# PWR.net
KiCad netlist of a schematic drawn in Altium Designer
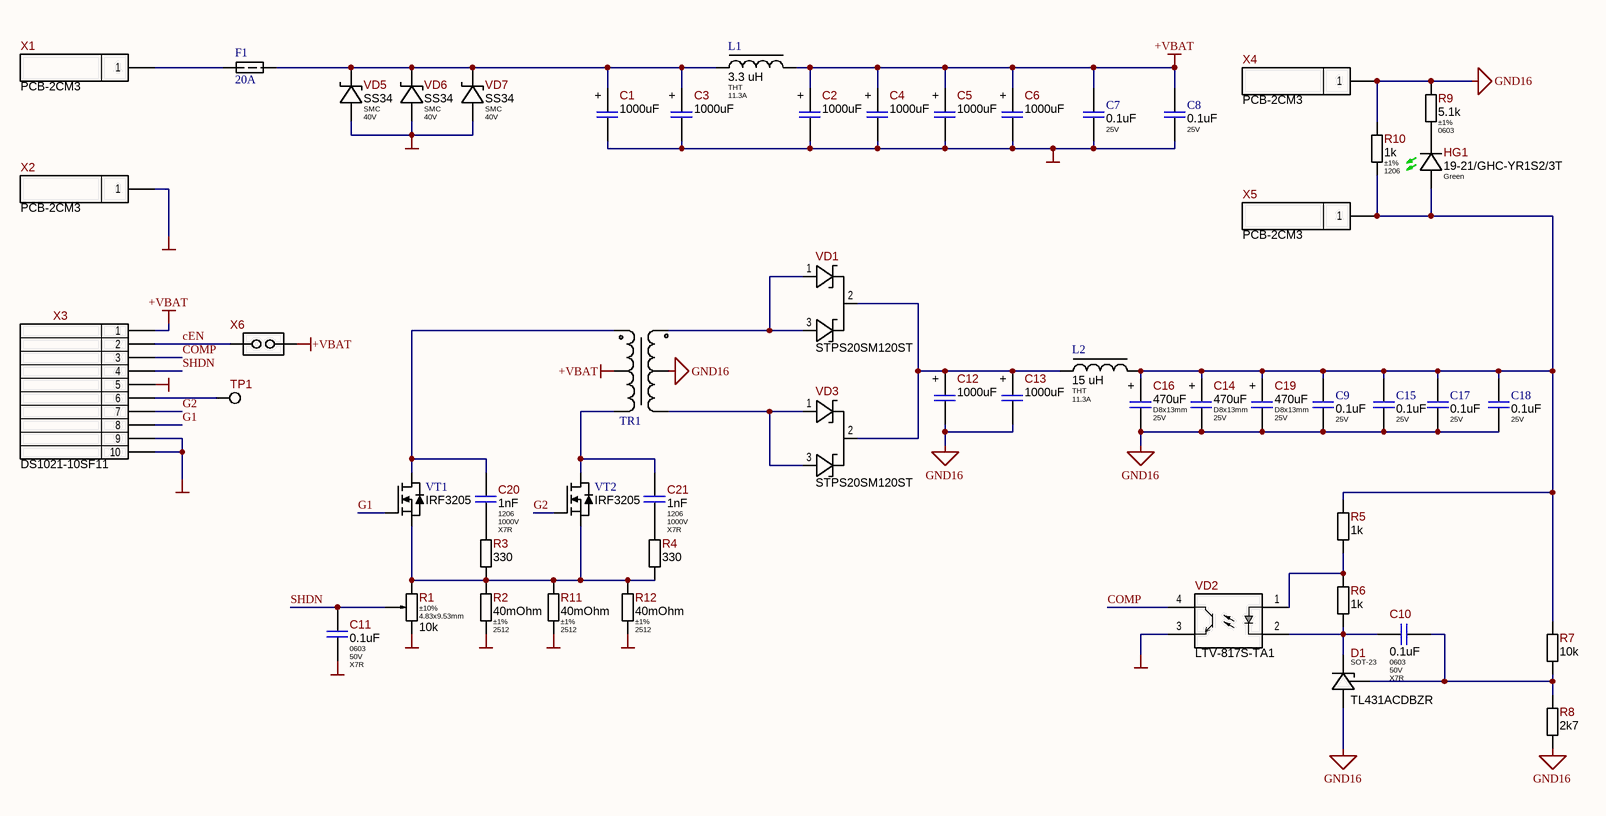
[diagram p0: PWR.SchDoc]

(export (version "E")
  (design (tool "Eeschema 10.0.6"))
  (components
    (comp (ref "C1")
      (value "1000uF")
      (footprint "CAP-AE-PTH-100D05x200H20")
      (description "1000uF 25V ±20% Aluminum Electrolytic Capacitors Radial, 2000 Hrs @ 105°C, 740mA Ripple Current")
      (fields (field (name "VOLTAGE") "25V") (field (name "PART NUMBER") "ESH108M025AH4AA"))
      (libsource (lib "capacitors") (part "ESH108M025AH4AA"))
    )
    (comp (ref "C2")
      (value "1000uF")
      (footprint "CAP-AE-PTH-100D05x200H20")
      (description "1000uF 25V ±20% Aluminum Electrolytic Capacitors Radial, 2000 Hrs @ 105°C, 740mA Ripple Current")
      (fields (field (name "VOLTAGE") "25V") (field (name "PART NUMBER") "ESH108M025AH4AA"))
      (libsource (lib "capacitors") (part "ESH108M025AH4AA"))
    )
    (comp (ref "C3")
      (value "1000uF")
      (footprint "CAP-AE-PTH-100D05x200H20")
      (description "1000uF 25V ±20% Aluminum Electrolytic Capacitors Radial, 2000 Hrs @ 105°C, 740mA Ripple Current")
      (fields (field (name "VOLTAGE") "25V") (field (name "PART NUMBER") "ESH108M025AH4AA"))
      (libsource (lib "capacitors") (part "ESH108M025AH4AA"))
    )
    (comp (ref "C4")
      (value "1000uF")
      (footprint "CAP-AE-PTH-100D05x200H20")
      (description "1000uF 25V ±20% Aluminum Electrolytic Capacitors Radial, 2000 Hrs @ 105°C, 740mA Ripple Current")
      (fields (field (name "VOLTAGE") "25V") (field (name "PART NUMBER") "ESH108M025AH4AA"))
      (libsource (lib "capacitors") (part "ESH108M025AH4AA"))
    )
    (comp (ref "C5")
      (value "1000uF")
      (footprint "CAP-AE-PTH-100D05x200H20")
      (description "1000uF 25V ±20% Aluminum Electrolytic Capacitors Radial, 2000 Hrs @ 105°C, 740mA Ripple Current")
      (fields (field (name "VOLTAGE") "25V") (field (name "PART NUMBER") "ESH108M025AH4AA"))
      (libsource (lib "capacitors") (part "ESH108M025AH4AA"))
    )
    (comp (ref "C6")
      (value "1000uF")
      (footprint "CAP-AE-PTH-100D05x200H20")
      (description "1000uF 25V ±20% Aluminum Electrolytic Capacitors Radial, 2000 Hrs @ 105°C, 740mA Ripple Current")
      (fields (field (name "VOLTAGE") "25V") (field (name "PART NUMBER") "ESH108M025AH4AA"))
      (libsource (lib "capacitors") (part "ESH108M025AH4AA"))
    )
    (comp (ref "C7")
      (value "0.1uF")
      (footprint "CAP: MKS2 (W=2.50MM)")
      (description "Multilayer Ceramic Capacitors MLCC - SMD/SMT 10 uF 25 VDC 10% 1206 X7R")
      (fields
        (field (name "MANUFACTURER") "Murata")
        (field (name "PART NUMBER") "GRM31CR71E106KA12L")
        (field (name "VOLTAGE") "25V")
      )
      (libsource (lib "vitech_capacitors") (part "CAP_NON_POLAR_THT"))
    )
    (comp (ref "C8")
      (value "0.1uF")
      (footprint "CAP: MKS2 (W=2.50MM)")
      (description "Multilayer Ceramic Capacitors MLCC - SMD/SMT 10 uF 25 VDC 10% 1206 X7R")
      (fields
        (field (name "MANUFACTURER") "Murata")
        (field (name "PART NUMBER") "GRM31CR71E106KA12L")
        (field (name "VOLTAGE") "25V")
      )
      (libsource (lib "vitech_capacitors") (part "CAP_NON_POLAR_THT"))
    )
    (comp (ref "C9")
      (value "0.1uF")
      (footprint "CAP: MKS2 (W=2.50MM)")
      (description "Multilayer Ceramic Capacitors MLCC - SMD/SMT 10 uF 25 VDC 10% 1206 X7R")
      (fields
        (field (name "MANUFACTURER") "Murata")
        (field (name "PART NUMBER") "GRM31CR71E106KA12L")
        (field (name "VOLTAGE") "25V")
      )
      (libsource (lib "vitech_capacitors") (part "CAP_NON_POLAR_THT"))
    )
    (comp (ref "C10")
      (value "0.1uF")
      (footprint "C_CERAMIC_0603_MED")
      (description "100nF 50V X7R ±10% 0603 Ceramic Capacitor RoHS")
      (fields
        (field (name "PACKAGE") "0603")
        (field (name "VOLTAGE") "50V")
        (field (name "DIELECTRIC TYPE") "X7R")
        (field (name "PART NUMBER") "CL10B104KB8NNNC")
        (field (name "MANUFACTURER") "Samsung Electro-Mechanics")
      )
      (libsource (lib "capacitors") (part "CL10B104KB8NNNC"))
    )
    (comp (ref "C11")
      (value "0.1uF")
      (footprint "C_CERAMIC_0603_MED")
      (description "100nF 50V X7R ±10% 0603 Ceramic Capacitor RoHS")
      (fields
        (field (name "PACKAGE") "0603")
        (field (name "VOLTAGE") "50V")
        (field (name "DIELECTRIC TYPE") "X7R")
        (field (name "PART NUMBER") "CL10B104KB8NNNC")
        (field (name "MANUFACTURER") "Samsung Electro-Mechanics")
      )
      (libsource (lib "capacitors") (part "CL10B104KB8NNNC"))
    )
    (comp (ref "C12")
      (value "1000uF")
      (footprint "CAP-AE-PTH-100D05x200H20")
      (description "1000uF 25V ±20% Aluminum Electrolytic Capacitors Radial, 2000 Hrs @ 105°C, 740mA Ripple Current")
      (fields (field (name "VOLTAGE") "25V") (field (name "PART NUMBER") "ESH108M025AH4AA"))
      (libsource (lib "capacitors") (part "ESH108M025AH4AA"))
    )
    (comp (ref "C13")
      (value "1000uF")
      (footprint "CAP-AE-PTH-100D05x200H20")
      (description "1000uF 25V ±20% Aluminum Electrolytic Capacitors Radial, 2000 Hrs @ 105°C, 740mA Ripple Current")
      (fields (field (name "VOLTAGE") "25V") (field (name "PART NUMBER") "ESH108M025AH4AA"))
      (libsource (lib "capacitors") (part "ESH108M025AH4AA"))
    )
    (comp (ref "C14")
      (value "470uF")
      (footprint "CAP-AE-PTH-80D05x130H15")
      (fields
        (field (name "PACKAGE") "D8x13mm")
        (field (name "VOLTAGE") "25V")
        (field (name "PART NUMBER") "KS-025V471MF130")
        (field (name "MANUFACTURER") "Koshin")
        (field (name "TOLERANCE") "±20%")
      )
      (libsource (lib "capacitors") (part "KS-025V471MF130"))
    )
    (comp (ref "C15")
      (value "0.1uF")
      (footprint "CAP: MKS2 (W=2.50MM)")
      (description "Multilayer Ceramic Capacitors MLCC - SMD/SMT 10 uF 25 VDC 10% 1206 X7R")
      (fields
        (field (name "MANUFACTURER") "Murata")
        (field (name "PART NUMBER") "GRM31CR71E106KA12L")
        (field (name "VOLTAGE") "25V")
      )
      (libsource (lib "vitech_capacitors") (part "CAP_NON_POLAR_THT"))
    )
    (comp (ref "C16")
      (value "470uF")
      (footprint "CAP-AE-PTH-80D05x130H15")
      (fields
        (field (name "PACKAGE") "D8x13mm")
        (field (name "VOLTAGE") "25V")
        (field (name "PART NUMBER") "KS-025V471MF130")
        (field (name "MANUFACTURER") "Koshin")
        (field (name "TOLERANCE") "±20%")
      )
      (libsource (lib "capacitors") (part "KS-025V471MF130"))
    )
    (comp (ref "C17")
      (value "0.1uF")
      (footprint "CAP: MKS2 (W=2.50MM)")
      (description "Multilayer Ceramic Capacitors MLCC - SMD/SMT 10 uF 25 VDC 10% 1206 X7R")
      (fields
        (field (name "MANUFACTURER") "Murata")
        (field (name "PART NUMBER") "GRM31CR71E106KA12L")
        (field (name "VOLTAGE") "25V")
      )
      (libsource (lib "vitech_capacitors") (part "CAP_NON_POLAR_THT"))
    )
    (comp (ref "C18")
      (value "0.1uF")
      (footprint "CAP: MKS2 (W=2.50MM)")
      (description "Multilayer Ceramic Capacitors MLCC - SMD/SMT 10 uF 25 VDC 10% 1206 X7R")
      (fields
        (field (name "MANUFACTURER") "Murata")
        (field (name "PART NUMBER") "GRM31CR71E106KA12L")
        (field (name "VOLTAGE") "25V")
      )
      (libsource (lib "vitech_capacitors") (part "CAP_NON_POLAR_THT"))
    )
    (comp (ref "C19")
      (value "470uF")
      (footprint "CAP-AE-PTH-80D05x130H15")
      (fields
        (field (name "PACKAGE") "D8x13mm")
        (field (name "VOLTAGE") "25V")
        (field (name "PART NUMBER") "KS-025V471MF130")
        (field (name "MANUFACTURER") "Koshin")
        (field (name "TOLERANCE") "±20%")
      )
      (libsource (lib "capacitors") (part "KS-025V471MF130"))
    )
    (comp (ref "C20")
      (value "1nF")
      (footprint "C_CERAMIC_1206_MED")
      (description "1nF 1000V X7R ±10% 1206 Ceramic Capacitor RoHS")
      (fields
        (field (name "PACKAGE") "1206")
        (field (name "VOLTAGE") "1000V")
        (field (name "DIELECTRIC TYPE") "X7R")
        (field (name "PART NUMBER") "1206B102K102CG")
        (field (name "MANUFACTURER") "Walsin")
      )
      (libsource (lib "capacitors") (part "1206B102K102CG"))
    )
    (comp (ref "C21")
      (value "1nF")
      (footprint "C_CERAMIC_1206_MED")
      (description "1nF 1000V X7R ±10% 1206 Ceramic Capacitor RoHS")
      (fields
        (field (name "PACKAGE") "1206")
        (field (name "VOLTAGE") "1000V")
        (field (name "DIELECTRIC TYPE") "X7R")
        (field (name "PART NUMBER") "1206B102K102CG")
        (field (name "MANUFACTURER") "Walsin")
      )
      (libsource (lib "capacitors") (part "1206B102K102CG"))
    )
    (comp (ref "D1")
      (value "TL431ACDBZR")
      (footprint "SOT-23_MED")
      (description "Adjustable Precision Shunt Regulator, Accuracy 1%,  SOT-23-3")
      (fields
        (field (name "PACKAGE") "SOT-23")
        (field (name "PART NUMBER") "TL431ACDBZR")
        (field (name "MANUFACTURER") "Texas Instruments")
      )
      (libsource (lib "ic") (part "TL431ACDBZR"))
    )
    (comp (ref "F1")
      (value "20A")
      (footprint "MINI_FUSE")
      (description "Fuse MAXI Size")
      (fields (field (name "MANUFACTURER_PART_NUMBER") "17861640001"))
      (libsource (lib "vitech_fuses") (part "MINI_FUSE"))
    )
    (comp (ref "HG1")
      (value "19-21/GHC-YR1S2/3T")
      (footprint "LED-0603G-0.8mm")
      (description "Indication LED, Green 528nm, Clear, SMD 0603, Vf 2.7-3.7V, 112 - 285mcd @ 20mA, 110°")
      (fields
        (field (name "MANUFACTURER") "Everlight Electronics")
        (field (name "PART NUMBER") "19-21/GHC-YR1S2/3T")
        (field (name "COLOR") "Green")
      )
      (libsource (lib "opto") (part "19-21/GHC-YR1S2/3T"))
    )
    (comp (ref "L1")
      (value "3.3 uH")
      (footprint "DROD0625V-18-1.12")
      (description "Дросель з магазину Coretech")
      (fields
        (field (name "MANUFACTURER") "Bourns Inc.")
        (field (name "PART NUMBER") "RLB0914-3R3ML-ND")
        (field (name "PACKAGE") "THT")
        (field (name "CURRENT") "11.3A")
      )
      (libsource (lib "vitech_inductors") (part "DROD0625V-18-1.12"))
    )
    (comp (ref "L2")
      (value "15 uH")
      (footprint "IND: R22.9/14/7.62 (H)")
      (fields
        (field (name "MANUFACTURER") "Bourns Inc.")
        (field (name "PART NUMBER") "RLB0914-3R3ML-ND")
        (field (name "TOLERANCE") "±20%")
        (field (name "PACKAGE") "THT")
        (field (name "CURRENT") "11.3A")
      )
      (libsource (lib "vitech_inductors") (part "IND_TOROIDAL"))
    )
    (comp (ref "R1")
      (value "10k")
      (footprint "3296W-1-xxx")
      (description "10 kOhms ±10% Trimmer Resistor, 0.5W, Through Hole 3/8\", 4.83x9.53mm, 10.03mm Height")
      (fields
        (field (name "TOLERANCE") "±10%")
        (field (name "PACKAGE") "4.83x9.53mm")
        (field (name "PART NUMBER") "3296W-1-103LF")
        (field (name "MANUFACTURER") "Bourns")
      )
      (libsource (lib "resistors") (part "3296W-1-103LF"))
    )
    (comp (ref "R2")
      (value "40mOhm")
      (footprint "CRA2512-Series")
      (description "30 mOhms ±1%, 3W 2512 Metal Strip Current Sense Chip Resistor")
      (fields
        (field (name "TOLERANCE") "±1%")
        (field (name "PACKAGE") "2512")
        (field (name "PART NUMBER") "CRA2512-FZ-R030ELF")
        (field (name "MANUFACTURER") "Bourns")
      )
      (libsource (lib "resistors") (part "CRA2512-FZ-R030ELF"))
    )
    (comp (ref "R3")
      (value "330")
      (footprint "R_ANY_CHIP_1206_MED")
      (description "75 Ohms ±1%, 1/4W 1206 Thick Film Resistor")
      (fields (field (name "TOLERANCE") "±1%") (field (name "PART NUMBER") "CRCW120675R0FKEAC"))
      (libsource (lib "resistors") (part "CRCW120675R0FKEAC"))
    )
    (comp (ref "R4")
      (value "330")
      (footprint "R_ANY_CHIP_1206_MED")
      (description "75 Ohms ±1%, 1/4W 1206 Thick Film Resistor")
      (fields (field (name "TOLERANCE") "±1%") (field (name "PART NUMBER") "CRCW120675R0FKEAC"))
      (libsource (lib "resistors") (part "CRCW120675R0FKEAC"))
    )
    (comp (ref "R5")
      (value "1k")
      (footprint "R_ANY_CHIP_0805_MED")
      (description "22 Ohms ±5%, 1/8W 0805 Thick Film Resistor")
      (fields (field (name "TOLERANCE") "±5%") (field (name "PART NUMBER") "RC0805JR-0722RL"))
      (libsource (lib "resistors") (part "RC0805JR-0722RL"))
    )
    (comp (ref "R6")
      (value "1k")
      (footprint "R_ANY_CHIP_0805_MED")
      (description "22 Ohms ±5%, 1/8W 0805 Thick Film Resistor")
      (fields (field (name "TOLERANCE") "±5%") (field (name "PART NUMBER") "RC0805JR-0722RL"))
      (libsource (lib "resistors") (part "RC0805JR-0722RL"))
    )
    (comp (ref "R7")
      (value "10k")
      (footprint "R_ANY_CHIP_0805_MED")
      (fields
        (field (name "TOLERANCE") "±5%")
        (field (name "PART NUMBER") "RC0805JR-0722RL")
        (field (name "MANUFACTURER") "Yageo")
      )
      (libsource (lib "resistors") (part "RC0805JR-0722RL"))
    )
    (comp (ref "R8")
      (value "2k7")
      (footprint "R_ANY_CHIP_0805_MED")
      (description "22 Ohms ±5%, 1/8W 0805 Thick Film Resistor")
      (fields (field (name "TOLERANCE") "±5%") (field (name "PART NUMBER") "RC0805JR-0722RL"))
      (libsource (lib "resistors") (part "RC0805JR-0722RL"))
    )
    (comp (ref "R9")
      (value "5.1k")
      (footprint "R_ANY_CHIP_0603_MED")
      (description "5.1 kOhms ±1%, 1/10W 0603 Thick Film Resistor")
      (fields
        (field (name "TOLERANCE") "±1%")
        (field (name "PACKAGE") "0603")
        (field (name "PART NUMBER") "RC0603FR-075K1L")
        (field (name "MANUFACTURER") "Yageo")
      )
      (libsource (lib "resistors") (part "RC0603FR-075K1L"))
    )
    (comp (ref "R10")
      (value "1k")
      (footprint "R_ANY_CHIP_1206_MED")
      (description "75 Ohms ±1%, 1/4W 1206 Thick Film Resistor")
      (fields
        (field (name "TOLERANCE") "±1%")
        (field (name "PACKAGE") "1206")
        (field (name "PART NUMBER") "CRCW120675R0FKEAC")
        (field (name "MANUFACTURER") "Vishay")
      )
      (libsource (lib "resistors") (part "CRCW120675R0FKEAC"))
    )
    (comp (ref "R11")
      (value "40mOhm")
      (footprint "CRA2512-Series")
      (description "30 mOhms ±1%, 3W 2512 Metal Strip Current Sense Chip Resistor")
      (fields
        (field (name "TOLERANCE") "±1%")
        (field (name "PACKAGE") "2512")
        (field (name "PART NUMBER") "CRA2512-FZ-R030ELF")
        (field (name "MANUFACTURER") "Bourns")
      )
      (libsource (lib "resistors") (part "CRA2512-FZ-R030ELF"))
    )
    (comp (ref "R12")
      (value "40mOhm")
      (footprint "CRA2512-Series")
      (description "30 mOhms ±1%, 3W 2512 Metal Strip Current Sense Chip Resistor")
      (fields
        (field (name "TOLERANCE") "±1%")
        (field (name "PACKAGE") "2512")
        (field (name "PART NUMBER") "CRA2512-FZ-R030ELF")
        (field (name "MANUFACTURER") "Bourns")
      )
      (libsource (lib "resistors") (part "CRA2512-FZ-R030ELF"))
    )
    (comp (ref "TP1")
      (value "PAD-1.1mm")
      (footprint "PAD-1.1mm")
      (description "1.1mm Pad for Plug-In or Receptacle")
      (fields (field (name "MANUFACTURER") "NONE"))
      (libsource (lib "probetools") (part "PAD-1.1mm"))
    )
    (comp (ref "TR1")
      (value "TR")
      (footprint "TR: R32.8/20.1/10.7 (L) - MINPOINT- 2")
      (fields
        (field (name "MANUFACTURER") "Handmade")
        (field (name "PART NUMBER") "RLB0914-3R3ML-ND")
        (field (name "TOLERANCE") "±20%")
      )
      (libsource (lib "vitech_inductors") (part "Toroidal Transformator Midpoint_1"))
    )
    (comp (ref "VD1")
      (value "STPS20SM120ST")
      (footprint "TO220(H)")
      (description "Diode Schottky Array 1 Pair Common Cathode, 120V 20A, TO-220")
      (fields
        (field (name "VOLTAGE") "120V")
        (field (name "MANUFACTURER") "STMicroelectronics")
        (field (name "PART NUMBER") "STPS20SM120ST")
      )
      (libsource (lib "vitech_semiconductors") (part "DIODE SCHOTTKY DUAL"))
    )
    (comp (ref "VD2")
      (value "LTV-817S-TA1")
      (footprint "LTV-817S-TA1_REC")
      (description "1-Channel Photocoupler, 5kV, SSOP-4")
      (fields
        (field (name "PART NUMBER") "LTV-817S-TA1")
        (field (name "MANUFACTURER") "Lite-On Optoelectronics")
      )
      (libsource (lib "opto") (part "LTV-817S-TA1"))
    )
    (comp (ref "VD3")
      (value "STPS20SM120ST")
      (footprint "TO220(H)")
      (description "Diode Schottky Array 1 Pair Common Cathode, 120V 20A, TO-220")
      (fields
        (field (name "VOLTAGE") "120V")
        (field (name "MANUFACTURER") "STMicroelectronics")
        (field (name "PART NUMBER") "STPS20SM120ST")
      )
      (libsource (lib "vitech_semiconductors") (part "DIODE SCHOTTKY DUAL"))
    )
    (comp (ref "VD5")
      (value "SS34")
      (footprint "SMC")
      (description "Diode Schottky 40V 3A, SMC")
      (fields
        (field (name "PART NUMBER") "SS34")
        (field (name "PACKAGE") "SMC")
        (field (name "VOLTAGE") "40V")
        (field (name "MANUFACTURER") "Onsemi")
      )
      (libsource (lib "diodes") (part "SS34"))
    )
    (comp (ref "VD6")
      (value "SS34")
      (footprint "SMC")
      (description "Diode Schottky 40V 3A, SMC")
      (fields
        (field (name "PART NUMBER") "SS34")
        (field (name "PACKAGE") "SMC")
        (field (name "VOLTAGE") "40V")
        (field (name "MANUFACTURER") "Onsemi")
      )
      (libsource (lib "diodes") (part "SS34"))
    )
    (comp (ref "VD7")
      (value "SS34")
      (footprint "SMC")
      (description "Diode Schottky 40V 3A, SMC")
      (fields
        (field (name "PART NUMBER") "SS34")
        (field (name "PACKAGE") "SMC")
        (field (name "VOLTAGE") "40V")
        (field (name "MANUFACTURER") "Onsemi")
      )
      (libsource (lib "diodes") (part "SS34"))
    )
    (comp (ref "VT1")
      (value "AOD403")
      (footprint "TO220(H)")
      (description "N-MOSFET; полевой;")
      (fields (field (name "PART NUMBER") "IRF3205"))
      (libsource (lib "vitech_semiconductors") (part "N-CH_MOSFET"))
    )
    (comp (ref "VT2")
      (value "AOD403")
      (footprint "TO220(H)")
      (description "N-MOSFET; полевой;")
      (fields (field (name "PART NUMBER") "IRF3205"))
      (libsource (lib "vitech_semiconductors") (part "N-CH_MOSFET"))
    )
    (comp (ref "X1")
      (value "PCB-2CM3")
      (footprint "CON: 8191")
      (fields (field (name "MANUFACTURER") "China") (field (name "PART NUMBER") "PCB-2CM3"))
      (libsource (lib "vitech_connectors") (part "PCB-2CM3"))
    )
    (comp (ref "X2")
      (value "PCB-2CM3")
      (footprint "CON: 8191")
      (fields (field (name "MANUFACTURER") "China") (field (name "PART NUMBER") "PCB-2CM3"))
      (libsource (lib "vitech_connectors") (part "PCB-2CM3"))
    )
    (comp (ref "X3")
      (value "PLS-10 (Part of PLS-40)")
      (footprint "DS1021-10S")
      (description "10 Pin 2.54mm Male Header, Vertical, 3mm and 6.1mm, PLS-5")
      (fields (field (name "PART NUMBER") "DS1021-10SF11") (field (name "MANUFACTURER") "Connfly"))
      (libsource (lib "connectors") (part "DS1021-10SF11"))
    )
    (comp (ref "X4")
      (value "PCB-2CM3")
      (footprint "CON: 8191")
      (fields (field (name "MANUFACTURER") "China") (field (name "PART NUMBER") "PCB-2CM3"))
      (libsource (lib "vitech_connectors") (part "PCB-2CM3"))
    )
    (comp (ref "X5")
      (value "PCB-2CM3")
      (footprint "CON: 8191")
      (fields (field (name "MANUFACTURER") "China") (field (name "PART NUMBER") "PCB-2CM3"))
      (libsource (lib "vitech_connectors") (part "PCB-2CM3"))
    )
    (comp (ref "X6")
      (value "PLS-2R U-Type")
      (footprint "DS1022-1x2RUx1")
      (description "2 pin Male Header, Right Angle, 2.54mm, PTH, PLS-2R, U-type")
      (fields (field (name "PART NUMBER") "DS1022-1x2RUF1") (field (name "MANUFACTURER") "Connfly"))
      (libsource (lib "connectors") (part "DS1022-1x2RUF1"))
    )
  )
  (nets
    (net (code "1") (name "+VBAT") (class "Default")
      (node (ref "C2") (pin "1") (pinfunction "1_1") (pintype "passive"))
      (node (ref "C4") (pin "1") (pinfunction "1_1") (pintype "passive"))
      (node (ref "C5") (pin "1") (pinfunction "1_1") (pintype "passive"))
      (node (ref "C6") (pin "1") (pinfunction "1_1") (pintype "passive"))
      (node (ref "C7") (pin "1") (pinfunction "1_1") (pintype "passive"))
      (node (ref "C8") (pin "1") (pinfunction "1_1") (pintype "passive"))
      (node (ref "L1") (pin "2") (pintype "passive"))
      (node (ref "TR1") (pin "3") (pintype "passive"))
      (node (ref "X3") (pin "1") (pinfunction "1_1") (pintype "passive"))
      (node (ref "X6") (pin "1") (pintype "passive"))
    )
    (net (code "2") (name "/COMP") (class "Default")
      (node (ref "VD2") (pin "4") (pinfunction "Collector_4") (pintype "passive"))
      (node (ref "X3") (pin "3") (pinfunction "3_3") (pintype "passive"))
    )
    (net (code "3") (name "/G1") (class "Default")
      (node (ref "VT1") (pin "1") (pinfunction "G_1") (pintype "passive"))
      (node (ref "X3") (pin "8") (pinfunction "8_8") (pintype "passive"))
    )
    (net (code "4") (name "/G2") (class "Default")
      (node (ref "VT2") (pin "1") (pinfunction "G_1") (pintype "passive"))
      (node (ref "X3") (pin "7") (pinfunction "7_7") (pintype "passive"))
    )
    (net (code "5") (name "/SHDN") (class "Default")
      (node (ref "C11") (pin "1") (pinfunction "1_1") (pintype "passive"))
      (node (ref "R1") (pin "2") (pinfunction "WIPER_2") (pintype "passive"))
      (node (ref "X3") (pin "4") (pinfunction "4_4") (pintype "passive"))
    )
    (net (code "6") (name "/cEN") (class "Default")
      (node (ref "X3") (pin "2") (pinfunction "2_2") (pintype "passive"))
      (node (ref "X6") (pin "2") (pintype "passive"))
    )
    (net (code "7") (name "GND") (class "Default")
      (node (ref "C1") (pin "2") (pinfunction "2_2") (pintype "passive"))
      (node (ref "C11") (pin "2") (pinfunction "2_2") (pintype "passive"))
      (node (ref "C2") (pin "2") (pinfunction "2_2") (pintype "passive"))
      (node (ref "C3") (pin "2") (pinfunction "2_2") (pintype "passive"))
      (node (ref "C4") (pin "2") (pinfunction "2_2") (pintype "passive"))
      (node (ref "C5") (pin "2") (pinfunction "2_2") (pintype "passive"))
      (node (ref "C6") (pin "2") (pinfunction "2_2") (pintype "passive"))
      (node (ref "C7") (pin "2") (pinfunction "2_2") (pintype "passive"))
      (node (ref "C8") (pin "2") (pinfunction "2_2") (pintype "passive"))
      (node (ref "R1") (pin "1") (pinfunction "CCW_1") (pintype "passive"))
      (node (ref "R11") (pin "2") (pintype "passive"))
      (node (ref "R12") (pin "2") (pintype "passive"))
      (node (ref "R2") (pin "2") (pintype "passive"))
      (node (ref "VD2") (pin "3") (pinfunction "Emitter_3") (pintype "passive"))
      (node (ref "VD5") (pin "AN") (pintype "passive"))
      (node (ref "VD6") (pin "AN") (pintype "passive"))
      (node (ref "VD7") (pin "AN") (pintype "passive"))
      (node (ref "X2") (pin "1") (pinfunction "1_1") (pintype "passive"))
      (node (ref "X3") (pin "10") (pinfunction "10_10") (pintype "passive"))
      (node (ref "X3") (pin "5") (pinfunction "5_5") (pintype "passive"))
      (node (ref "X3") (pin "9") (pinfunction "9_9") (pintype "passive"))
    )
    (net (code "8") (name "GND16") (class "Default")
      (node (ref "C12") (pin "2") (pinfunction "2_2") (pintype "passive"))
      (node (ref "C13") (pin "2") (pinfunction "2_2") (pintype "passive"))
      (node (ref "C14") (pin "2") (pinfunction "2_2") (pintype "passive"))
      (node (ref "C15") (pin "2") (pinfunction "2_2") (pintype "passive"))
      (node (ref "C16") (pin "2") (pinfunction "2_2") (pintype "passive"))
      (node (ref "C17") (pin "2") (pinfunction "2_2") (pintype "passive"))
      (node (ref "C18") (pin "2") (pinfunction "2_2") (pintype "passive"))
      (node (ref "C19") (pin "2") (pinfunction "2_2") (pintype "passive"))
      (node (ref "C9") (pin "2") (pinfunction "2_2") (pintype "passive"))
      (node (ref "D1") (pin "3") (pinfunction "A_3") (pintype "passive"))
      (node (ref "R10") (pin "1") (pintype "passive"))
      (node (ref "R8") (pin "1") (pintype "passive"))
      (node (ref "R9") (pin "1") (pintype "passive"))
      (node (ref "TR1") (pin "6") (pintype "passive"))
      (node (ref "X4") (pin "1") (pinfunction "1_1") (pintype "passive"))
    )
    (net (code "9") (name "Net-(C1-Pad1)") (class "Default")
      (node (ref "C1") (pin "1") (pinfunction "1_1") (pintype "passive"))
      (node (ref "C3") (pin "1") (pinfunction "1_1") (pintype "passive"))
      (node (ref "F1") (pin "2") (pinfunction "2_2") (pintype "passive"))
      (node (ref "L1") (pin "1") (pintype "passive"))
      (node (ref "VD5") (pin "CA") (pintype "passive"))
      (node (ref "VD6") (pin "CA") (pintype "passive"))
      (node (ref "VD7") (pin "CA") (pintype "passive"))
    )
    (net (code "10") (name "Net-(C20-Pad2)") (class "Default")
      (node (ref "C20") (pin "2") (pinfunction "2_2") (pintype "passive"))
      (node (ref "R3") (pin "1") (pintype "passive"))
    )
    (net (code "11") (name "Net-(C21-Pad2)") (class "Default")
      (node (ref "C21") (pin "2") (pinfunction "2_2") (pintype "passive"))
      (node (ref "R4") (pin "1") (pintype "passive"))
    )
    (net (code "12") (name "Net-(D1-C)") (class "Default")
      (node (ref "C10") (pin "1") (pinfunction "1_1") (pintype "passive"))
      (node (ref "D1") (pin "1") (pinfunction "C_1") (pintype "passive"))
      (node (ref "R6") (pin "1") (pintype "passive"))
      (node (ref "VD2") (pin "2") (pinfunction "Cathode_2") (pintype "passive"))
    )
    (net (code "13") (name "Net-(D1-REF)") (class "Default")
      (node (ref "C10") (pin "2") (pinfunction "2_2") (pintype "passive"))
      (node (ref "D1") (pin "2") (pinfunction "REF_2") (pintype "passive"))
      (node (ref "R7") (pin "1") (pintype "passive"))
      (node (ref "R8") (pin "2") (pintype "passive"))
    )
    (net (code "14") (name "Net-(F1-Pad1)") (class "Default")
      (node (ref "F1") (pin "1") (pinfunction "1_1") (pintype "passive"))
      (node (ref "X1") (pin "1") (pinfunction "1_1") (pintype "passive"))
    )
    (net (code "15") (name "Net-(HG1-Anode)") (class "Default")
      (node (ref "C14") (pin "1") (pinfunction "1_1") (pintype "passive"))
      (node (ref "C15") (pin "1") (pinfunction "1_1") (pintype "passive"))
      (node (ref "C16") (pin "1") (pinfunction "1_1") (pintype "passive"))
      (node (ref "C17") (pin "1") (pinfunction "1_1") (pintype "passive"))
      (node (ref "C18") (pin "1") (pinfunction "1_1") (pintype "passive"))
      (node (ref "C19") (pin "1") (pinfunction "1_1") (pintype "passive"))
      (node (ref "C9") (pin "1") (pinfunction "1_1") (pintype "passive"))
      (node (ref "HG1") (pin "AN") (pinfunction "Anode_AN") (pintype "passive"))
      (node (ref "L2") (pin "2") (pintype "passive"))
      (node (ref "R10") (pin "2") (pintype "passive"))
      (node (ref "R5") (pin "2") (pintype "passive"))
      (node (ref "R7") (pin "2") (pintype "passive"))
      (node (ref "X5") (pin "1") (pinfunction "1_1") (pintype "passive"))
    )
    (net (code "16") (name "Net-(HG1-Cathode)") (class "Default")
      (node (ref "HG1") (pin "CA") (pinfunction "Cathode_CA") (pintype "passive"))
      (node (ref "R9") (pin "2") (pintype "passive"))
    )
    (net (code "17") (name "Net-(R1-CW)") (class "Default")
      (node (ref "R1") (pin "3") (pinfunction "CW_3") (pintype "passive"))
      (node (ref "R11") (pin "1") (pintype "passive"))
      (node (ref "R12") (pin "1") (pintype "passive"))
      (node (ref "R2") (pin "1") (pintype "passive"))
      (node (ref "R3") (pin "2") (pintype "passive"))
      (node (ref "R4") (pin "2") (pintype "passive"))
      (node (ref "VT1") (pin "3") (pinfunction "S_3") (pintype "passive"))
      (node (ref "VT2") (pin "3") (pinfunction "S_3") (pintype "passive"))
    )
    (net (code "18") (name "Net-(TP1-Pad1)") (class "Default")
      (node (ref "TP1") (pin "1") (pintype "passive"))
      (node (ref "X3") (pin "6") (pinfunction "6_6") (pintype "passive"))
    )
    (net (code "19") (name "Net-(VD1-Anode_1)") (class "Default")
      (node (ref "TR1") (pin "4") (pintype "passive"))
      (node (ref "VD1") (pin "1") (pinfunction "Anode_1_1") (pintype "passive"))
      (node (ref "VD1") (pin "3") (pinfunction "Anode_2_3") (pintype "passive"))
    )
    (net (code "20") (name "Net-(VD1-Cathode)") (class "Default")
      (node (ref "C12") (pin "1") (pinfunction "1_1") (pintype "passive"))
      (node (ref "C13") (pin "1") (pinfunction "1_1") (pintype "passive"))
      (node (ref "L2") (pin "1") (pintype "passive"))
      (node (ref "VD1") (pin "2") (pinfunction "Cathode_2") (pintype "passive"))
      (node (ref "VD3") (pin "2") (pinfunction "Cathode_2") (pintype "passive"))
    )
    (net (code "21") (name "Net-(VD2-Anode)") (class "Default")
      (node (ref "R5") (pin "1") (pintype "passive"))
      (node (ref "R6") (pin "2") (pintype "passive"))
      (node (ref "VD2") (pin "1") (pinfunction "Anode_1") (pintype "passive"))
    )
    (net (code "22") (name "Net-(VD3-Anode_1)") (class "Default")
      (node (ref "TR1") (pin "5") (pintype "passive"))
      (node (ref "VD3") (pin "1") (pinfunction "Anode_1_1") (pintype "passive"))
      (node (ref "VD3") (pin "3") (pinfunction "Anode_2_3") (pintype "passive"))
    )
    (net (code "23") (name "Net-(VT1-D)") (class "Default")
      (node (ref "C20") (pin "1") (pinfunction "1_1") (pintype "passive"))
      (node (ref "TR1") (pin "1") (pintype "passive"))
      (node (ref "VT1") (pin "2") (pinfunction "D_2") (pintype "passive"))
    )
    (net (code "24") (name "Net-(VT2-D)") (class "Default")
      (node (ref "C21") (pin "1") (pinfunction "1_1") (pintype "passive"))
      (node (ref "TR1") (pin "2") (pintype "passive"))
      (node (ref "VT2") (pin "2") (pinfunction "D_2") (pintype "passive"))
    )
  )
)
